# Kernal64Cart.net
KiCad netlist of a schematic drawn in EAGLE
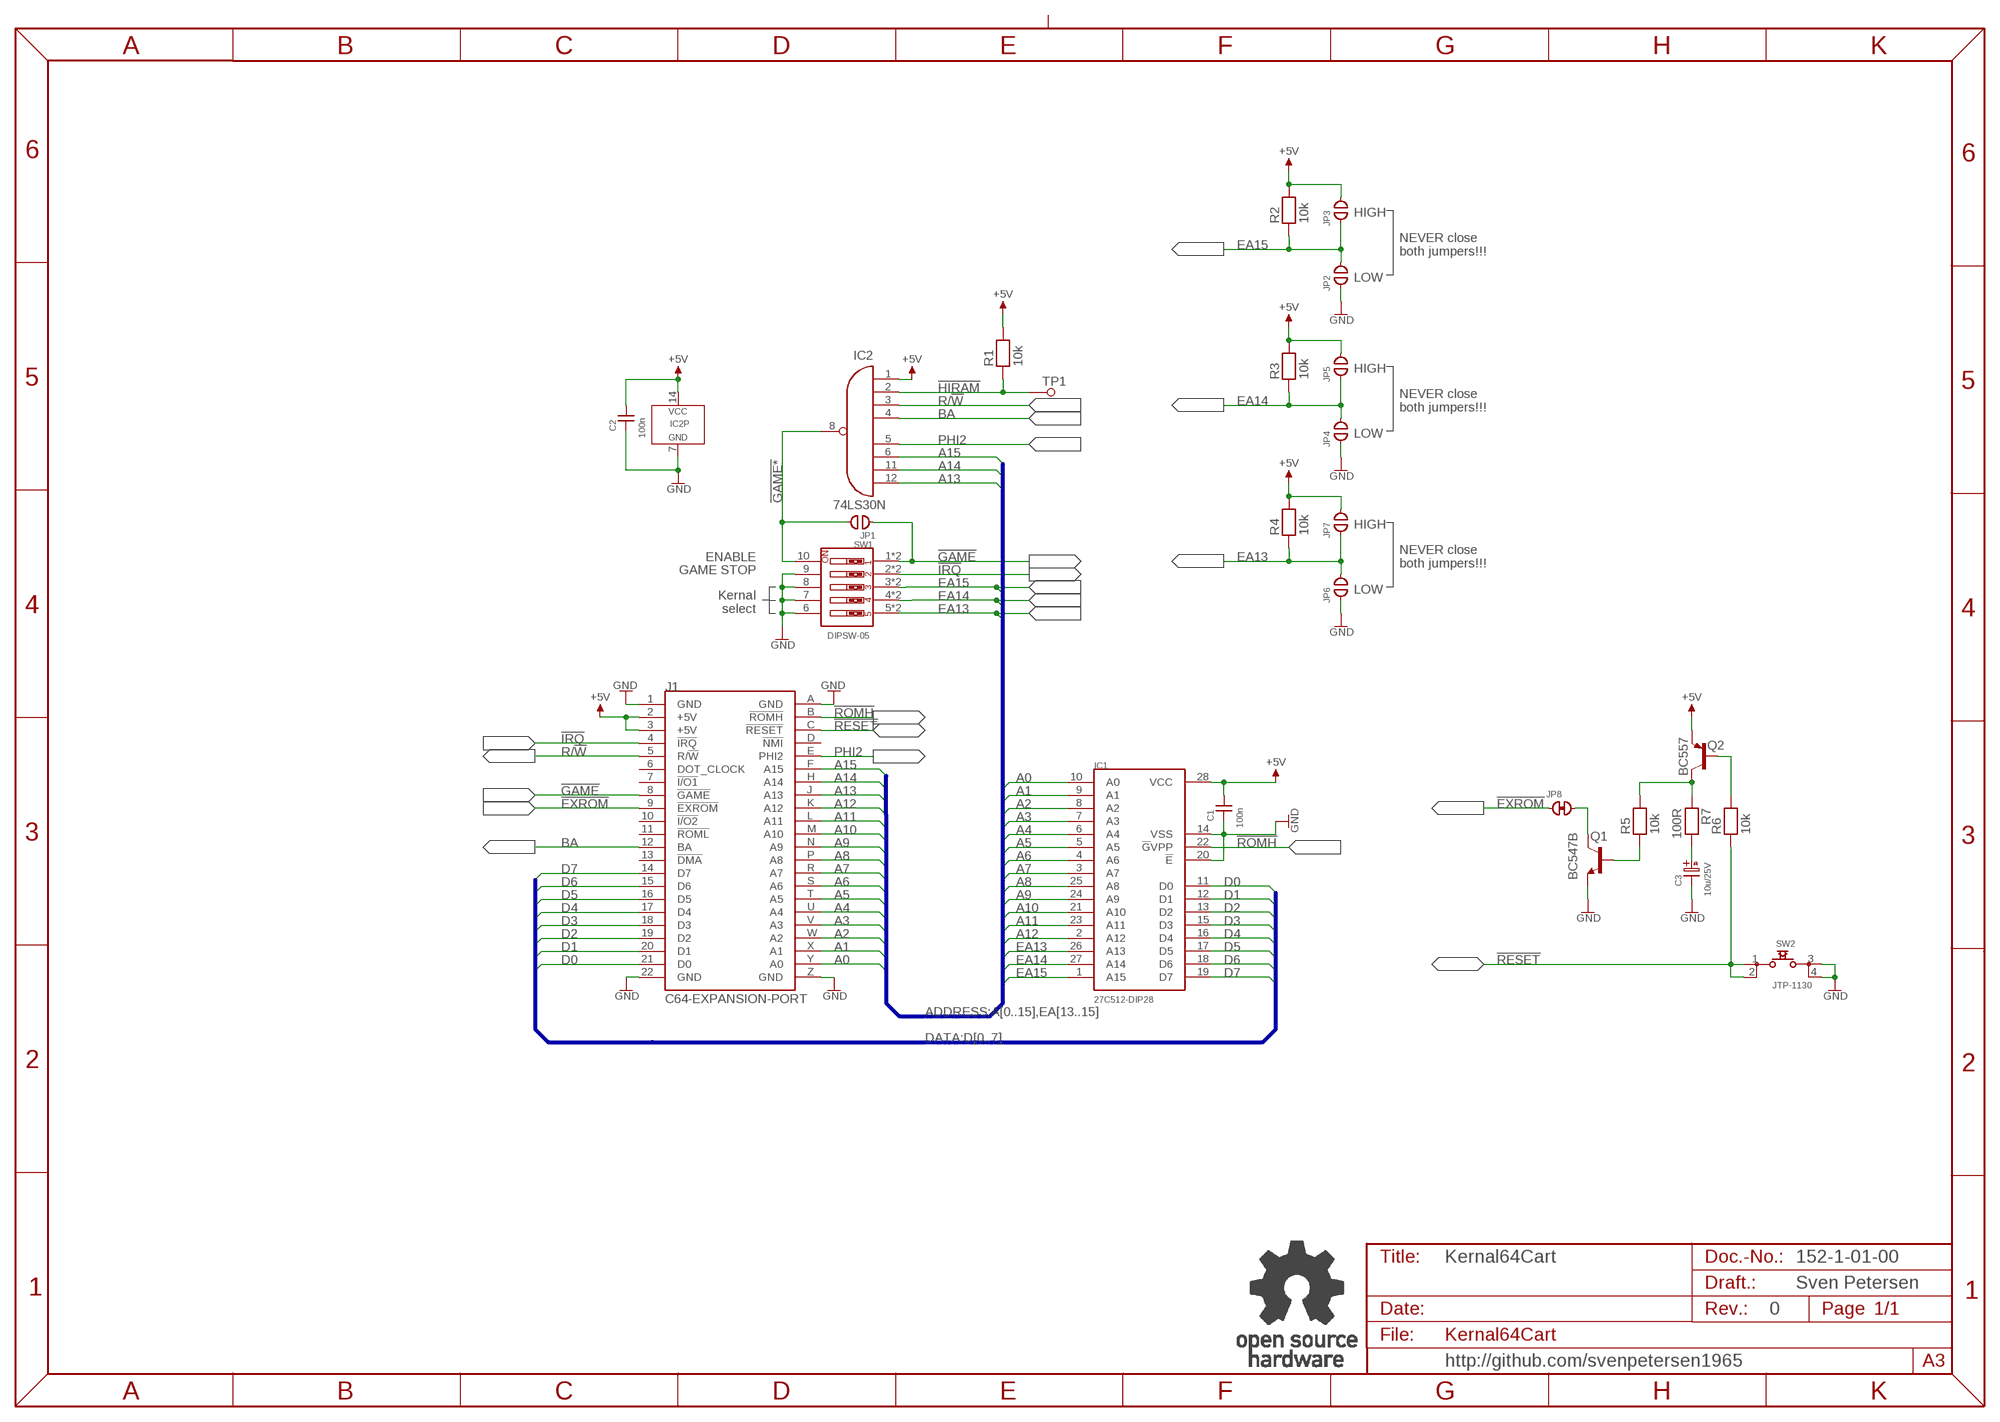
[diagram p0: schematic, sheet 1]

(export (version "E")
  (design (tool "Eeschema 10.0.6"))
  (components
    (comp (ref "C1")
      (value "100n")
      (footprint "eagle-import:C-2,5")
      (libsource (lib "eagle-import") (part "CAP01"))
    )
    (comp (ref "C2")
      (value "100n")
      (footprint "eagle-import:C-2,5")
      (libsource (lib "eagle-import") (part "CAP01"))
    )
    (comp (ref "C3")
      (value "10u/25V")
      (footprint "eagle-import:C5,0_2,0")
      (libsource (lib "eagle-import") (part "C05,0/2,0"))
    )
    (comp (ref "IC1")
      (value "27C512-DIP28")
      (footprint "eagle-import:DIL28-6")
      (libsource (lib "eagle-import") (part "M27C512-DIP28"))
    )
    (comp (ref "IC2")
      (value "74LS30N")
      (footprint "eagle-import:DIL-14")
      (libsource (lib "eagle-import") (part "7430DIP"))
    )
    (comp (ref "J1")
      (value "C64-EXPANSION-PORT")
      (footprint "eagle-import:EXPANSIO_SQ")
      (libsource (lib "eagle-import") (part "C64-EXPANSIONPNARROW"))
    )
    (comp (ref "JP1")
      (value "OPEN")
      (footprint "eagle-import:CP_OP")
      (libsource (lib "eagle-import") (part "OPEN"))
    )
    (comp (ref "JP2")
      (value "OPEN")
      (footprint "eagle-import:CP_OP")
      (libsource (lib "eagle-import") (part "OPEN"))
    )
    (comp (ref "JP3")
      (value "OPEN")
      (footprint "eagle-import:CP_OP")
      (libsource (lib "eagle-import") (part "OPEN"))
    )
    (comp (ref "JP4")
      (value "OPEN")
      (footprint "eagle-import:CP_OP")
      (libsource (lib "eagle-import") (part "OPEN"))
    )
    (comp (ref "JP5")
      (value "OPEN")
      (footprint "eagle-import:CP_OP")
      (libsource (lib "eagle-import") (part "OPEN"))
    )
    (comp (ref "JP6")
      (value "OPEN")
      (footprint "eagle-import:CP_OP")
      (libsource (lib "eagle-import") (part "OPEN"))
    )
    (comp (ref "JP7")
      (value "OPEN")
      (footprint "eagle-import:CP_OP")
      (libsource (lib "eagle-import") (part "OPEN"))
    )
    (comp (ref "JP8")
      (value "CLOSED")
      (footprint "eagle-import:CP_CL")
      (libsource (lib "eagle-import") (part "CLOSED"))
    )
    (comp (ref "Q1")
      (value "BC547B")
      (footprint "eagle-import:TO92")
      (libsource (lib "eagle-import") (part "BC547B"))
    )
    (comp (ref "Q2")
      (value "BC557")
      (footprint "eagle-import:TO92")
      (libsource (lib "eagle-import") (part "BC557"))
    )
    (comp (ref "R1")
      (value "10k")
      (footprint "eagle-import:R-10")
      (libsource (lib "eagle-import") (part "RES04"))
    )
    (comp (ref "R2")
      (value "10k")
      (footprint "eagle-import:R-10")
      (libsource (lib "eagle-import") (part "RES04"))
    )
    (comp (ref "R3")
      (value "10k")
      (footprint "eagle-import:R-10")
      (libsource (lib "eagle-import") (part "RES04"))
    )
    (comp (ref "R4")
      (value "10k")
      (footprint "eagle-import:R-10")
      (libsource (lib "eagle-import") (part "RES04"))
    )
    (comp (ref "R5")
      (value "10k")
      (footprint "eagle-import:R-10")
      (libsource (lib "eagle-import") (part "RES04"))
    )
    (comp (ref "R6")
      (value "10k")
      (footprint "eagle-import:R-10")
      (libsource (lib "eagle-import") (part "RES04"))
    )
    (comp (ref "R7")
      (value "100R")
      (footprint "eagle-import:R-10")
      (libsource (lib "eagle-import") (part "RES04"))
    )
    (comp (ref "SW1")
      (value "DIPSW-05")
      (footprint "eagle-import:DIPSW-05VJ")
      (libsource (lib "eagle-import") (part "DIPSW-05"))
    )
    (comp (ref "SW2")
      (value "JTP-1130")
      (footprint "eagle-import:JTP-1130")
      (libsource (lib "eagle-import") (part "JTP-1130"))
    )
    (comp (ref "TP1")
      (value "1,3/2,0")
      (footprint "eagle-import:1,3_2,0")
      (libsource (lib "eagle-import") (part "1,3/2,0"))
    )
    (comp (ref "U$50")
      (value "OPEN_SOURCE_HW")
      (footprint "eagle-import:OPENHW")
      (libsource (lib "eagle-import") (part "OPEN_SOURCE_HW"))
    )
  )
  (nets
    (net (code "9") (name "+5V") (class "Default")
      (node (ref "C1") (pin "2") (pinfunction "2_2") (pintype "passive"))
      (node (ref "C2") (pin "2") (pinfunction "2_2") (pintype "passive"))
      (node (ref "IC1") (pin "28") (pinfunction "VCC_28") (pintype "power_in"))
      (node (ref "IC2") (pin "1") (pinfunction "I0_1") (pintype "input"))
      (node (ref "IC2") (pin "14") (pinfunction "VCC_14") (pintype "bidirectional"))
      (node (ref "J1") (pin "2") (pinfunction "+5V_2") (pintype "power_in"))
      (node (ref "J1") (pin "3") (pinfunction "+5V_3") (pintype "power_in"))
      (node (ref "JP3") (pin "2") (pinfunction "2_2") (pintype "passive"))
      (node (ref "JP5") (pin "2") (pinfunction "2_2") (pintype "passive"))
      (node (ref "JP7") (pin "2") (pinfunction "2_2") (pintype "passive"))
      (node (ref "Q2") (pin "1") (pinfunction "E_1") (pintype "passive"))
      (node (ref "R1") (pin "2") (pinfunction "2_2") (pintype "passive"))
      (node (ref "R2") (pin "2") (pinfunction "2_2") (pintype "passive"))
      (node (ref "R3") (pin "2") (pinfunction "2_2") (pintype "passive"))
      (node (ref "R4") (pin "2") (pinfunction "2_2") (pintype "passive"))
    )
    (net (code "10") (name "/A0") (class "Default")
      (node (ref "IC1") (pin "10") (pinfunction "A0_10") (pintype "input"))
      (node (ref "J1") (pin "Y") (pinfunction "A0_Y") (pintype "bidirectional"))
    )
    (net (code "11") (name "/A1") (class "Default")
      (node (ref "IC1") (pin "9") (pinfunction "A1_9") (pintype "input"))
      (node (ref "J1") (pin "X") (pinfunction "A1_X") (pintype "bidirectional"))
    )
    (net (code "12") (name "/A2") (class "Default")
      (node (ref "IC1") (pin "8") (pinfunction "A2_8") (pintype "input"))
      (node (ref "J1") (pin "W") (pinfunction "A2_W") (pintype "bidirectional"))
    )
    (net (code "13") (name "/A3") (class "Default")
      (node (ref "IC1") (pin "7") (pinfunction "A3_7") (pintype "input"))
      (node (ref "J1") (pin "V") (pinfunction "A3_V") (pintype "bidirectional"))
    )
    (net (code "14") (name "/A4") (class "Default")
      (node (ref "IC1") (pin "6") (pinfunction "A4_6") (pintype "input"))
      (node (ref "J1") (pin "U") (pinfunction "A4_U") (pintype "bidirectional"))
    )
    (net (code "15") (name "/A5") (class "Default")
      (node (ref "IC1") (pin "5") (pinfunction "A5_5") (pintype "input"))
      (node (ref "J1") (pin "T") (pinfunction "A5_T") (pintype "bidirectional"))
    )
    (net (code "16") (name "/A6") (class "Default")
      (node (ref "IC1") (pin "4") (pinfunction "A6_4") (pintype "input"))
      (node (ref "J1") (pin "S") (pinfunction "A6_S") (pintype "bidirectional"))
    )
    (net (code "17") (name "/A7") (class "Default")
      (node (ref "IC1") (pin "3") (pinfunction "A7_3") (pintype "input"))
      (node (ref "J1") (pin "R") (pinfunction "A7_R") (pintype "bidirectional"))
    )
    (net (code "18") (name "/A8") (class "Default")
      (node (ref "IC1") (pin "25") (pinfunction "A8_25") (pintype "input"))
      (node (ref "J1") (pin "P") (pinfunction "A8_P") (pintype "bidirectional"))
    )
    (net (code "19") (name "/A9") (class "Default")
      (node (ref "IC1") (pin "24") (pinfunction "A9_24") (pintype "input"))
      (node (ref "J1") (pin "N") (pinfunction "A9_N") (pintype "bidirectional"))
    )
    (net (code "20") (name "/A10") (class "Default")
      (node (ref "IC1") (pin "21") (pinfunction "A10_21") (pintype "input"))
      (node (ref "J1") (pin "M") (pinfunction "A10_M") (pintype "bidirectional"))
    )
    (net (code "21") (name "/A11") (class "Default")
      (node (ref "IC1") (pin "23") (pinfunction "A11_23") (pintype "input"))
      (node (ref "J1") (pin "L") (pinfunction "A11_L") (pintype "bidirectional"))
    )
    (net (code "22") (name "/A12") (class "Default")
      (node (ref "IC1") (pin "2") (pinfunction "A12_2") (pintype "input"))
      (node (ref "J1") (pin "K") (pinfunction "A12_K") (pintype "bidirectional"))
    )
    (net (code "23") (name "/A13") (class "Default")
      (node (ref "IC2") (pin "12") (pinfunction "I7_12") (pintype "input"))
      (node (ref "J1") (pin "J") (pinfunction "A13_J") (pintype "bidirectional"))
    )
    (net (code "24") (name "/A14") (class "Default")
      (node (ref "IC2") (pin "11") (pinfunction "I6_11") (pintype "input"))
      (node (ref "J1") (pin "H") (pinfunction "A14_H") (pintype "bidirectional"))
    )
    (net (code "25") (name "/A15") (class "Default")
      (node (ref "IC2") (pin "6") (pinfunction "I5_6") (pintype "input"))
      (node (ref "J1") (pin "F") (pinfunction "A15_F") (pintype "bidirectional"))
    )
    (net (code "26") (name "/BA") (class "Default")
      (node (ref "IC2") (pin "4") (pinfunction "I3_4") (pintype "input"))
      (node (ref "J1") (pin "12") (pinfunction "BA_12") (pintype "output"))
    )
    (net (code "27") (name "/D0") (class "Default")
      (node (ref "IC1") (pin "11") (pinfunction "D0_11") (pintype "bidirectional"))
      (node (ref "J1") (pin "21") (pinfunction "D0_21") (pintype "bidirectional"))
    )
    (net (code "28") (name "/D1") (class "Default")
      (node (ref "IC1") (pin "12") (pinfunction "D1_12") (pintype "bidirectional"))
      (node (ref "J1") (pin "20") (pinfunction "D1_20") (pintype "bidirectional"))
    )
    (net (code "29") (name "/D2") (class "Default")
      (node (ref "IC1") (pin "13") (pinfunction "D2_13") (pintype "bidirectional"))
      (node (ref "J1") (pin "19") (pinfunction "D2_19") (pintype "bidirectional"))
    )
    (net (code "30") (name "/D3") (class "Default")
      (node (ref "IC1") (pin "15") (pinfunction "D3_15") (pintype "bidirectional"))
      (node (ref "J1") (pin "18") (pinfunction "D3_18") (pintype "bidirectional"))
    )
    (net (code "31") (name "/D4") (class "Default")
      (node (ref "IC1") (pin "16") (pinfunction "D4_16") (pintype "bidirectional"))
      (node (ref "J1") (pin "17") (pinfunction "D4_17") (pintype "bidirectional"))
    )
    (net (code "32") (name "/D5") (class "Default")
      (node (ref "IC1") (pin "17") (pinfunction "D5_17") (pintype "bidirectional"))
      (node (ref "J1") (pin "16") (pinfunction "D5_16") (pintype "bidirectional"))
    )
    (net (code "33") (name "/D6") (class "Default")
      (node (ref "IC1") (pin "18") (pinfunction "D6_18") (pintype "bidirectional"))
      (node (ref "J1") (pin "15") (pinfunction "D6_15") (pintype "bidirectional"))
    )
    (net (code "34") (name "/D7") (class "Default")
      (node (ref "IC1") (pin "19") (pinfunction "D7_19") (pintype "bidirectional"))
      (node (ref "J1") (pin "14") (pinfunction "D7_14") (pintype "bidirectional"))
    )
    (net (code "36") (name "/EA13") (class "Default")
      (node (ref "IC1") (pin "26") (pinfunction "A13_26") (pintype "input"))
      (node (ref "JP6") (pin "2") (pinfunction "2_2") (pintype "passive"))
      (node (ref "JP7") (pin "1") (pinfunction "1_1") (pintype "passive"))
      (node (ref "R4") (pin "1") (pinfunction "1_1") (pintype "passive"))
      (node (ref "SW1") (pin "5") (pinfunction "5_5") (pintype "passive"))
      (node (ref "SW1") (pin "5J") (pinfunction "5_5J") (pintype "passive"))
    )
    (net (code "37") (name "/EA14") (class "Default")
      (node (ref "IC1") (pin "27") (pinfunction "A14_27") (pintype "input"))
      (node (ref "JP4") (pin "2") (pinfunction "2_2") (pintype "passive"))
      (node (ref "JP5") (pin "1") (pinfunction "1_1") (pintype "passive"))
      (node (ref "R3") (pin "1") (pinfunction "1_1") (pintype "passive"))
      (node (ref "SW1") (pin "4") (pinfunction "4_4") (pintype "passive"))
      (node (ref "SW1") (pin "4J") (pinfunction "4_4J") (pintype "passive"))
    )
    (net (code "38") (name "/EA15") (class "Default")
      (node (ref "IC1") (pin "1") (pinfunction "A15_1") (pintype "input"))
      (node (ref "JP2") (pin "2") (pinfunction "2_2") (pintype "passive"))
      (node (ref "JP3") (pin "1") (pinfunction "1_1") (pintype "passive"))
      (node (ref "R2") (pin "1") (pinfunction "1_1") (pintype "passive"))
      (node (ref "SW1") (pin "3") (pinfunction "3_3") (pintype "passive"))
      (node (ref "SW1") (pin "3J") (pinfunction "3_3J") (pintype "passive"))
    )
    (net (code "39") (name "/PHI2") (class "Default")
      (node (ref "IC2") (pin "5") (pinfunction "I4_5") (pintype "input"))
      (node (ref "J1") (pin "E") (pinfunction "PHI2_E") (pintype "output"))
    )
    (net (code "40") (name "/R{slash}~{W}") (class "Default")
      (node (ref "IC2") (pin "3") (pinfunction "I2_3") (pintype "input"))
      (node (ref "J1") (pin "5") (pinfunction "R/~{W}_5") (pintype "output"))
    )
    (net (code "42") (name "/~{EXROM}") (class "Default")
      (node (ref "J1") (pin "9") (pinfunction "~{EXROM}_9") (pintype "input"))
      (node (ref "JP8") (pin "1") (pinfunction "1_1") (pintype "passive"))
    )
    (net (code "43") (name "/~{GAME*}") (class "Default")
      (node (ref "IC2") (pin "8") (pinfunction "O_8") (pintype "output"))
      (node (ref "JP1") (pin "2") (pinfunction "2_2") (pintype "passive"))
      (node (ref "SW1") (pin "10") (pinfunction "10_10") (pintype "passive"))
    )
    (net (code "44") (name "/~{GAME}") (class "Default")
      (node (ref "J1") (pin "8") (pinfunction "~{GAME}_8") (pintype "input"))
      (node (ref "JP1") (pin "1") (pinfunction "1_1") (pintype "passive"))
      (node (ref "SW1") (pin "1") (pinfunction "1_1") (pintype "passive"))
      (node (ref "SW1") (pin "1J") (pinfunction "1_1J") (pintype "passive"))
    )
    (net (code "45") (name "/~{HIRAM}") (class "Default")
      (node (ref "IC2") (pin "2") (pinfunction "I1_2") (pintype "input"))
      (node (ref "R1") (pin "1") (pinfunction "1_1") (pintype "passive"))
      (node (ref "TP1") (pin "1") (pinfunction "1_1") (pintype "passive"))
    )
    (net (code "46") (name "/~{IRQ}") (class "Default")
      (node (ref "J1") (pin "4") (pinfunction "~{IRQ}_4") (pintype "input"))
      (node (ref "SW1") (pin "2") (pinfunction "2_2") (pintype "passive"))
      (node (ref "SW1") (pin "2J") (pinfunction "2_2J") (pintype "passive"))
    )
    (net (code "47") (name "/~{RESET}") (class "Default")
      (node (ref "J1") (pin "C") (pinfunction "~{RESET}_C") (pintype "open_collector"))
      (node (ref "R6") (pin "1") (pinfunction "1_1") (pintype "passive"))
      (node (ref "SW2") (pin "1") (pinfunction "1_1") (pintype "passive"))
      (node (ref "SW2") (pin "2") (pinfunction "2_2") (pintype "passive"))
    )
    (net (code "48") (name "/~{ROMH}") (class "Default")
      (node (ref "IC1") (pin "22") (pinfunction "~{G}VPP_22") (pintype "input"))
      (node (ref "J1") (pin "B") (pinfunction "~{ROMH}_B") (pintype "output"))
    )
    (net (code "49") (name "GND") (class "Default")
      (node (ref "C1") (pin "1") (pinfunction "1_1") (pintype "passive"))
      (node (ref "C2") (pin "1") (pinfunction "1_1") (pintype "passive"))
      (node (ref "C3") (pin "K") (pinfunction "-_K") (pintype "passive"))
      (node (ref "IC1") (pin "14") (pinfunction "VSS_14") (pintype "power_in"))
      (node (ref "IC1") (pin "20") (pinfunction "~{E}_20") (pintype "input"))
      (node (ref "IC2") (pin "7") (pinfunction "GND_7") (pintype "bidirectional"))
      (node (ref "J1") (pin "1") (pinfunction "GND_1") (pintype "power_in"))
      (node (ref "J1") (pin "22") (pinfunction "GND_22") (pintype "power_in"))
      (node (ref "J1") (pin "A") (pinfunction "GND_A") (pintype "power_in"))
      (node (ref "J1") (pin "Z") (pinfunction "GND_Z") (pintype "power_in"))
      (node (ref "JP2") (pin "1") (pinfunction "1_1") (pintype "passive"))
      (node (ref "JP4") (pin "1") (pinfunction "1_1") (pintype "passive"))
      (node (ref "JP6") (pin "1") (pinfunction "1_1") (pintype "passive"))
      (node (ref "Q1") (pin "1") (pinfunction "E_1") (pintype "passive"))
      (node (ref "SW1") (pin "6") (pinfunction "6_6") (pintype "passive"))
      (node (ref "SW1") (pin "7") (pinfunction "7_7") (pintype "passive"))
      (node (ref "SW1") (pin "8") (pinfunction "8_8") (pintype "passive"))
      (node (ref "SW1") (pin "9") (pinfunction "9_9") (pintype "passive"))
      (node (ref "SW2") (pin "3") (pinfunction "3_3") (pintype "passive"))
      (node (ref "SW2") (pin "4") (pinfunction "4_4") (pintype "passive"))
    )
    (net (code "50") (name "Net-(C3-+)") (class "Default")
      (node (ref "C3") (pin "A") (pinfunction "+_A") (pintype "passive"))
      (node (ref "R7") (pin "2") (pinfunction "2_2") (pintype "passive"))
    )
    (net (code "51") (name "Net-(Q1-B)") (class "Default")
      (node (ref "Q1") (pin "2") (pinfunction "B_2") (pintype "passive"))
      (node (ref "R5") (pin "1") (pinfunction "1_1") (pintype "passive"))
    )
    (net (code "52") (name "Net-(Q1-C)") (class "Default")
      (node (ref "JP8") (pin "2") (pinfunction "2_2") (pintype "passive"))
      (node (ref "Q1") (pin "3") (pinfunction "C_3") (pintype "passive"))
    )
    (net (code "53") (name "Net-(Q2-B)") (class "Default")
      (node (ref "Q2") (pin "2") (pinfunction "B_2") (pintype "passive"))
      (node (ref "R6") (pin "2") (pinfunction "2_2") (pintype "passive"))
    )
    (net (code "54") (name "Net-(Q2-C)") (class "Default")
      (node (ref "Q2") (pin "3") (pinfunction "C_3") (pintype "passive"))
      (node (ref "R5") (pin "2") (pinfunction "2_2") (pintype "passive"))
      (node (ref "R7") (pin "1") (pinfunction "1_1") (pintype "passive"))
    )
    (net (code "55") (name "unconnected-(J1-DOT_CLOCK-Pad6)") (class "Default")
      (node (ref "J1") (pin "6") (pinfunction "DOT_CLOCK_6") (pintype "output"))
    )
    (net (code "56") (name "unconnected-(J1-~{DMA}-Pad13)") (class "Default")
      (node (ref "J1") (pin "13") (pinfunction "~{DMA}_13") (pintype "input"))
    )
    (net (code "57") (name "unconnected-(J1-~{I{slash}O1}-Pad7)") (class "Default")
      (node (ref "J1") (pin "7") (pinfunction "~{I/O1}_7") (pintype "output"))
    )
    (net (code "58") (name "unconnected-(J1-~{I{slash}O2}-Pad10)") (class "Default")
      (node (ref "J1") (pin "10") (pinfunction "~{I/O2}_10") (pintype "output"))
    )
    (net (code "59") (name "unconnected-(J1-~{NMI}-PadD)") (class "Default")
      (node (ref "J1") (pin "D") (pinfunction "~{NMI}_D") (pintype "input"))
    )
    (net (code "60") (name "unconnected-(J1-~{ROML}-Pad11)") (class "Default")
      (node (ref "J1") (pin "11") (pinfunction "~{ROML}_11") (pintype "output"))
    )
  )
)
